# SparkFun_6DoF_LSM6DSO.net
KiCad netlist of a schematic drawn in EAGLE
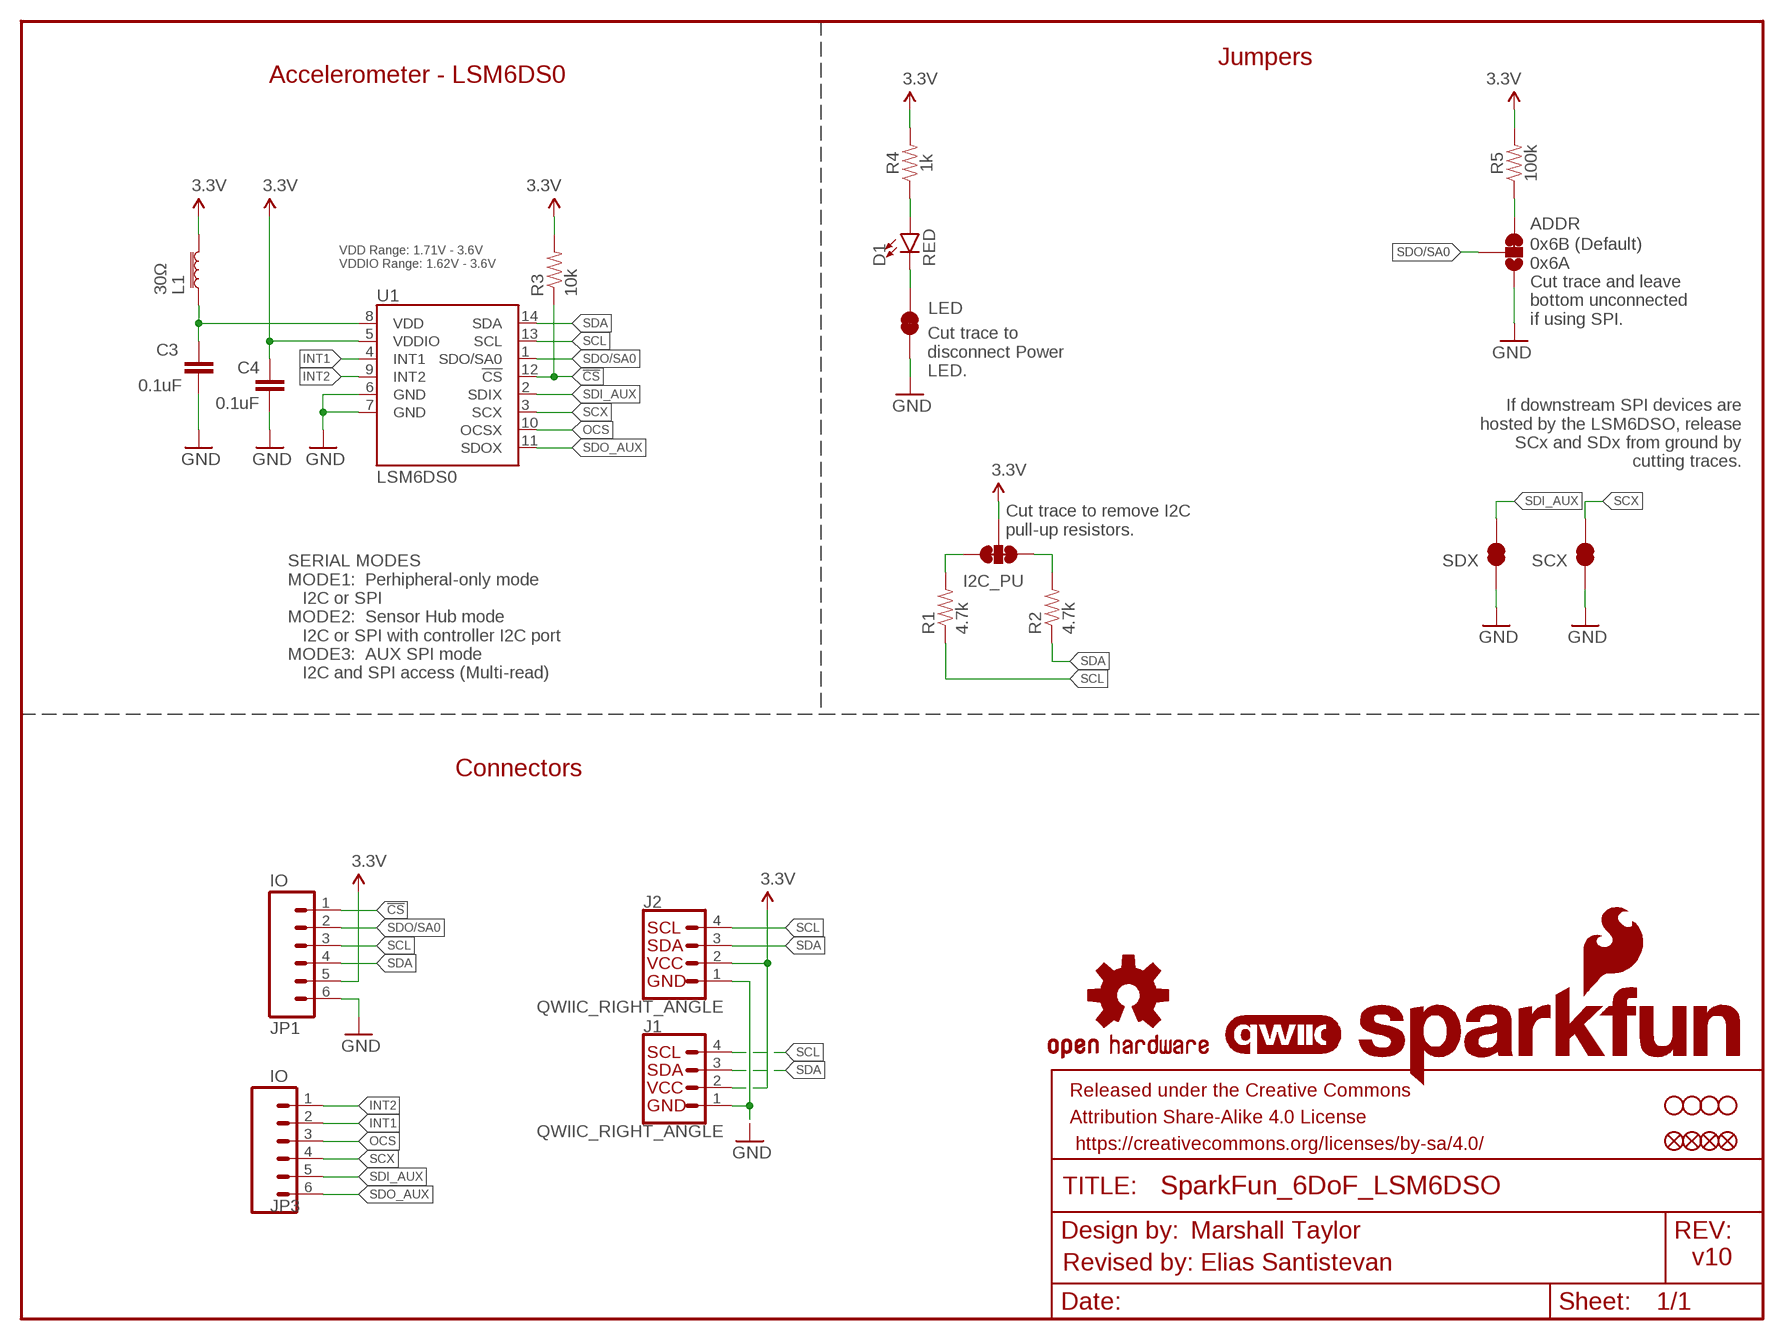
[diagram p0: schematic, sheet 1]

(export (version "E")
  (design (tool "Eeschema 10.0.6"))
  (components
    (comp (ref "ADDR")
      (value "JUMPER-SMT_3_1-NC_TRACE_SILK")
      (footprint "eagle-import:SMT-JUMPER_3_1-NC_TRACE_SILK")
      (libsource (lib "eagle-import") (part "JUMPER-SMT_3_1-NC_TRACE_SILK"))
    )
    (comp (ref "C3")
      (value "0.1uF")
      (footprint "eagle-import:0603")
      (libsource (lib "eagle-import") (part "0.1UF-0603-25V-(+80/-20%)"))
    )
    (comp (ref "C4")
      (value "0.1uF")
      (footprint "eagle-import:0603")
      (libsource (lib "eagle-import") (part "0.1UF-0603-25V-(+80/-20%)"))
    )
    (comp (ref "D1")
      (value "RED")
      (footprint "eagle-import:LED-0603")
      (libsource (lib "eagle-import") (part "LED-RED0603"))
    )
    (comp (ref "FD1")
      (value "FIDUCIALUFIDUCIAL")
      (footprint "eagle-import:FIDUCIAL-MICRO")
      (libsource (lib "eagle-import") (part "FIDUCIALUFIDUCIAL"))
    )
    (comp (ref "FD2")
      (value "FIDUCIALUFIDUCIAL")
      (footprint "eagle-import:FIDUCIAL-MICRO")
      (libsource (lib "eagle-import") (part "FIDUCIALUFIDUCIAL"))
    )
    (comp (ref "FID1")
      (value "FIDUCIALUFIDUCIAL")
      (footprint "eagle-import:FIDUCIAL-MICRO")
      (libsource (lib "eagle-import") (part "FIDUCIALUFIDUCIAL"))
    )
    (comp (ref "FID2")
      (value "FIDUCIALUFIDUCIAL")
      (footprint "eagle-import:FIDUCIAL-MICRO")
      (libsource (lib "eagle-import") (part "FIDUCIALUFIDUCIAL"))
    )
    (comp (ref "FRAME1")
      (value "FRAME-LETTER")
      (footprint "eagle-import:CREATIVE_COMMONS")
      (fields (field (name "DESIGNER") "Marshall Taylor"))
      (libsource (lib "eagle-import") (part "FRAME-LETTER"))
    )
    (comp (ref "I2C_PU")
      (value "S_MODE")
      (footprint "eagle-import:SMT-JUMPER_3_2-NC_TRACE_SILK")
      (libsource (lib "eagle-import") (part "JUMPER-SMT_3_2-NC_TRACE_SILK"))
    )
    (comp (ref "J1")
      (value "QWIIC_RIGHT_ANGLE")
      (footprint "eagle-import:JST04_1MM_RA")
      (libsource (lib "eagle-import") (part "QWIIC_CONNECTORJS-1MM"))
    )
    (comp (ref "J2")
      (value "QWIIC_RIGHT_ANGLE")
      (footprint "eagle-import:JST04_1MM_RA")
      (libsource (lib "eagle-import") (part "QWIIC_CONNECTORJS-1MM"))
    )
    (comp (ref "JP1")
      (value "IO")
      (footprint "eagle-import:1X06_NO_SILK")
      (libsource (lib "eagle-import") (part "CONN_06NO_SILK_NO_POP"))
    )
    (comp (ref "JP3")
      (value "IO")
      (footprint "eagle-import:1X06_NO_SILK")
      (libsource (lib "eagle-import") (part "CONN_06NO_SILK_NO_POP"))
    )
    (comp (ref "L1")
      (value "30Ω")
      (footprint "eagle-import:0603")
      (libsource (lib "eagle-import") (part "FERRITE_BEAD-0603-30OHM-100MHZ"))
    )
    (comp (ref "LED")
      (value "JUMPER-SMT_2_NC_TRACE_SILK")
      (footprint "eagle-import:SMT-JUMPER_2_NC_TRACE_SILK")
      (libsource (lib "eagle-import") (part "JUMPER-SMT_2_NC_TRACE_SILK"))
    )
    (comp (ref "LOGO1")
      (value "QWIIC_LOGO_4MM")
      (footprint "eagle-import:QWIIC_4MM")
      (libsource (lib "eagle-import") (part "QWIIC_LOGO_4MM"))
    )
    (comp (ref "LOGO2")
      (value "OSHW-LOGOS")
      (footprint "eagle-import:OSHW-LOGO-S")
      (libsource (lib "eagle-import") (part "OSHW-LOGOS"))
    )
    (comp (ref "LOGO3")
      (value "SFE_LOGO_NAME_FLAME.1_INCH")
      (footprint "eagle-import:SFE_LOGO_NAME_FLAME_.1")
      (libsource (lib "eagle-import") (part "SFE_LOGO_NAME_FLAME.1_INCH"))
    )
    (comp (ref "R1")
      (value "4.7k")
      (footprint "eagle-import:0603")
      (libsource (lib "eagle-import") (part "4.7KOHM-0603-1/10W-1%"))
    )
    (comp (ref "R2")
      (value "4.7k")
      (footprint "eagle-import:0603")
      (libsource (lib "eagle-import") (part "4.7KOHM-0603-1/10W-1%"))
    )
    (comp (ref "R3")
      (value "10k")
      (footprint "eagle-import:0603")
      (libsource (lib "eagle-import") (part "10KOHM-0603-1/10W-1%"))
    )
    (comp (ref "R4")
      (value "1k")
      (footprint "eagle-import:0603")
      (libsource (lib "eagle-import") (part "1KOHM-0603-1/10W-1%"))
    )
    (comp (ref "R5")
      (value "100k")
      (footprint "eagle-import:0603")
      (libsource (lib "eagle-import") (part "100KOHM-0603-1/10W-1%"))
    )
    (comp (ref "SCX")
      (value "JUMPER-SMT_2_NC_TRACE_SILK")
      (footprint "eagle-import:SMT-JUMPER_2_NC_TRACE_SILK")
      (libsource (lib "eagle-import") (part "JUMPER-SMT_2_NC_TRACE_SILK"))
    )
    (comp (ref "SDX")
      (value "JUMPER-SMT_2_NC_TRACE_SILK")
      (footprint "eagle-import:SMT-JUMPER_2_NC_TRACE_SILK")
      (libsource (lib "eagle-import") (part "JUMPER-SMT_2_NC_TRACE_SILK"))
    )
    (comp (ref "STANDOFF1")
      (value "STAND-OFFTIGHT")
      (footprint "eagle-import:STAND-OFF-TIGHT")
      (libsource (lib "eagle-import") (part "STAND-OFFTIGHT"))
    )
    (comp (ref "STANDOFF2")
      (value "STAND-OFFTIGHT")
      (footprint "eagle-import:STAND-OFF-TIGHT")
      (libsource (lib "eagle-import") (part "STAND-OFFTIGHT"))
    )
    (comp (ref "STANDOFF3")
      (value "STAND-OFFTIGHT")
      (footprint "eagle-import:STAND-OFF-TIGHT")
      (libsource (lib "eagle-import") (part "STAND-OFFTIGHT"))
    )
    (comp (ref "STANDOFF4")
      (value "STAND-OFFTIGHT")
      (footprint "eagle-import:STAND-OFF-TIGHT")
      (libsource (lib "eagle-import") (part "STAND-OFFTIGHT"))
    )
    (comp (ref "U1")
      (value "LSM6DS0")
      (footprint "eagle-import:LGA14L")
      (libsource (lib "eagle-import") (part "LSM6DSO"))
    )
  )
  (nets
    (net (code "1") (name "/~{CS}") (class "Default")
      (node (ref "JP1") (pin "1") (pinfunction "1_1") (pintype "passive"))
      (node (ref "R3") (pin "1") (pinfunction "1_1") (pintype "passive"))
      (node (ref "U1") (pin "12") (pinfunction "~{CS}_12") (pintype "bidirectional"))
    )
    (net (code "2") (name "3.3V") (class "Default")
      (node (ref "C4") (pin "1") (pinfunction "1_1") (pintype "passive"))
      (node (ref "I2C_PU") (pin "2") (pinfunction "2_2") (pintype "passive"))
      (node (ref "J1") (pin "2") (pinfunction "2_2") (pintype "power_in"))
      (node (ref "J2") (pin "2") (pinfunction "2_2") (pintype "power_in"))
      (node (ref "JP1") (pin "5") (pinfunction "5_5") (pintype "passive"))
      (node (ref "L1") (pin "1") (pinfunction "1_1") (pintype "passive"))
      (node (ref "R3") (pin "2") (pinfunction "2_2") (pintype "passive"))
      (node (ref "R4") (pin "2") (pinfunction "2_2") (pintype "passive"))
      (node (ref "R5") (pin "2") (pinfunction "2_2") (pintype "passive"))
      (node (ref "U1") (pin "5") (pinfunction "VDDIO_5") (pintype "bidirectional"))
    )
    (net (code "3") (name "GND") (class "Default")
      (node (ref "ADDR") (pin "1") (pinfunction "1_1") (pintype "passive"))
      (node (ref "C3") (pin "2") (pinfunction "2_2") (pintype "passive"))
      (node (ref "C4") (pin "2") (pinfunction "2_2") (pintype "passive"))
      (node (ref "J1") (pin "1") (pinfunction "1_1") (pintype "power_in"))
      (node (ref "J2") (pin "1") (pinfunction "1_1") (pintype "power_in"))
      (node (ref "JP1") (pin "6") (pinfunction "6_6") (pintype "passive"))
      (node (ref "LED") (pin "1") (pinfunction "1_1") (pintype "passive"))
      (node (ref "SCX") (pin "1") (pinfunction "1_1") (pintype "passive"))
      (node (ref "SDX") (pin "1") (pinfunction "1_1") (pintype "passive"))
      (node (ref "U1") (pin "6") (pinfunction "GND_6") (pintype "bidirectional"))
      (node (ref "U1") (pin "7") (pinfunction "GND_7") (pintype "bidirectional"))
    )
    (net (code "4") (name "INT1") (class "Default")
      (node (ref "JP3") (pin "2") (pinfunction "2_2") (pintype "passive"))
      (node (ref "U1") (pin "4") (pinfunction "INT1_4") (pintype "bidirectional"))
    )
    (net (code "5") (name "INT2") (class "Default")
      (node (ref "JP3") (pin "1") (pinfunction "1_1") (pintype "passive"))
      (node (ref "U1") (pin "9") (pinfunction "INT2_9") (pintype "bidirectional"))
    )
    (net (code "6") (name "Net-(ADDR-Pad3)") (class "Default")
      (node (ref "ADDR") (pin "3") (pinfunction "3_3") (pintype "passive"))
      (node (ref "R5") (pin "1") (pinfunction "1_1") (pintype "passive"))
    )
    (net (code "7") (name "Net-(D1-PadA)") (class "Default")
      (node (ref "D1") (pin "A") (pinfunction "A_A") (pintype "passive"))
      (node (ref "R4") (pin "1") (pinfunction "1_1") (pintype "passive"))
    )
    (net (code "8") (name "Net-(D1-PadC)") (class "Default")
      (node (ref "D1") (pin "C") (pinfunction "C_C") (pintype "passive"))
      (node (ref "LED") (pin "2") (pinfunction "2_2") (pintype "passive"))
    )
    (net (code "9") (name "Net-(I2C_PU-Pad1)") (class "Default")
      (node (ref "I2C_PU") (pin "1") (pinfunction "1_1") (pintype "passive"))
      (node (ref "R1") (pin "2") (pinfunction "2_2") (pintype "passive"))
    )
    (net (code "10") (name "Net-(I2C_PU-Pad3)") (class "Default")
      (node (ref "I2C_PU") (pin "3") (pinfunction "3_3") (pintype "passive"))
      (node (ref "R2") (pin "2") (pinfunction "2_2") (pintype "passive"))
    )
    (net (code "11") (name "Net-(U1-VDD)") (class "Default")
      (node (ref "C3") (pin "1") (pinfunction "1_1") (pintype "passive"))
      (node (ref "L1") (pin "2") (pinfunction "2_2") (pintype "passive"))
      (node (ref "U1") (pin "8") (pinfunction "VDD_8") (pintype "bidirectional"))
    )
    (net (code "12") (name "OCS") (class "Default")
      (node (ref "JP3") (pin "3") (pinfunction "3_3") (pintype "passive"))
      (node (ref "U1") (pin "10") (pinfunction "OCSX_10") (pintype "bidirectional"))
    )
    (net (code "13") (name "SCL") (class "Default")
      (node (ref "J1") (pin "4") (pinfunction "4_4") (pintype "passive"))
      (node (ref "J2") (pin "4") (pinfunction "4_4") (pintype "passive"))
      (node (ref "JP1") (pin "3") (pinfunction "3_3") (pintype "passive"))
      (node (ref "R1") (pin "1") (pinfunction "1_1") (pintype "passive"))
      (node (ref "U1") (pin "13") (pinfunction "SCL_13") (pintype "bidirectional"))
    )
    (net (code "14") (name "SCX") (class "Default")
      (node (ref "JP3") (pin "4") (pinfunction "4_4") (pintype "passive"))
      (node (ref "SCX") (pin "2") (pinfunction "2_2") (pintype "passive"))
      (node (ref "U1") (pin "3") (pinfunction "SCX_3") (pintype "bidirectional"))
    )
    (net (code "15") (name "SDA") (class "Default")
      (node (ref "J1") (pin "3") (pinfunction "3_3") (pintype "passive"))
      (node (ref "J2") (pin "3") (pinfunction "3_3") (pintype "passive"))
      (node (ref "JP1") (pin "4") (pinfunction "4_4") (pintype "passive"))
      (node (ref "R2") (pin "1") (pinfunction "1_1") (pintype "passive"))
      (node (ref "U1") (pin "14") (pinfunction "SDA_14") (pintype "bidirectional"))
    )
    (net (code "16") (name "SDI_AUX") (class "Default")
      (node (ref "JP3") (pin "5") (pinfunction "5_5") (pintype "passive"))
      (node (ref "SDX") (pin "2") (pinfunction "2_2") (pintype "passive"))
      (node (ref "U1") (pin "2") (pinfunction "SDIX_2") (pintype "bidirectional"))
    )
    (net (code "17") (name "SDO_AUX") (class "Default")
      (node (ref "JP3") (pin "6") (pinfunction "6_6") (pintype "passive"))
      (node (ref "U1") (pin "11") (pinfunction "SDOX_11") (pintype "bidirectional"))
    )
    (net (code "18") (name "SDO{slash}SA0") (class "Default")
      (node (ref "ADDR") (pin "2") (pinfunction "2_2") (pintype "passive"))
      (node (ref "JP1") (pin "2") (pinfunction "2_2") (pintype "passive"))
      (node (ref "U1") (pin "1") (pinfunction "SDO/SA0_1") (pintype "bidirectional"))
    )
  )
)
